# 3_amplifier.net
KiCad netlist of a schematic drawn in Altium Designer
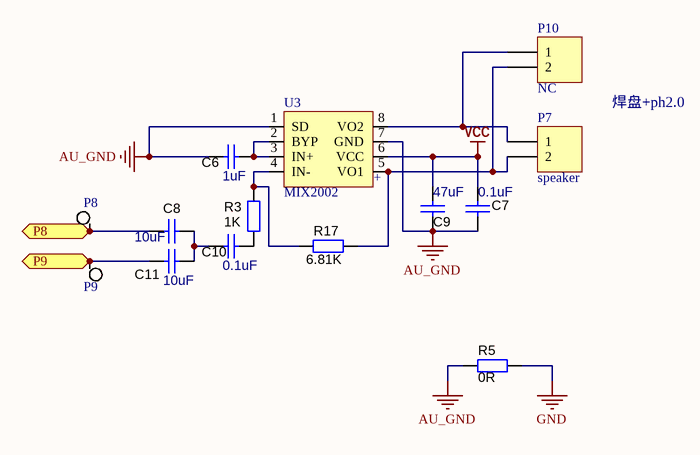
[diagram p0: 3 amplifier.SchDoc]

(export (version "E")
  (design (tool "Eeschema 10.0.6"))
  (components
    (comp (ref "C6")
      (value "1uF")
      (footprint "0402")
      (description "CAP, CERM, 0.01uF, 100V, +/-5%, X7R, 0603")
      (fields (field (name "PARTNUMBER") "06031C103JAT2A") (field (name "MANUFACTURER") "AVX"))
      (libsource (lib "03.常用器件") (part "CAP1_npol"))
    )
    (comp (ref "C7")
      (value "0.1uF")
      (footprint "0402")
      (description "CAP, CERM, 0.01uF, 100V, +/-5%, X7R, 0603")
      (fields (field (name "PARTNUMBER") "06031C103JAT2A") (field (name "MANUFACTURER") "AVX"))
      (libsource (lib "03.常用器件") (part "CAP1_npol"))
    )
    (comp (ref "C8")
      (value "10uF")
      (footprint "0603")
      (description "CAP, CERM, 0.01uF, 100V, +/-5%, X7R, 0603")
      (fields (field (name "PARTNUMBER") "06031C103JAT2A") (field (name "MANUFACTURER") "AVX"))
      (libsource (lib "03.常用器件") (part "CAP1_npol"))
    )
    (comp (ref "C9")
      (value "47uF")
      (footprint "0805")
      (description "CAP, CERM, 0.01uF, 100V, +/-5%, X7R, 0603")
      (fields (field (name "PARTNUMBER") "06031C103JAT2A") (field (name "MANUFACTURER") "AVX"))
      (libsource (lib "03.常用器件") (part "CAP1_npol"))
    )
    (comp (ref "C10")
      (value "0.1uF")
      (footprint "0402")
      (description "CAP, CERM, 0.01uF, 100V, +/-5%, X7R, 0603")
      (fields (field (name "PARTNUMBER") "06031C103JAT2A") (field (name "MANUFACTURER") "AVX"))
      (libsource (lib "03.常用器件") (part "CAP1_npol"))
    )
    (comp (ref "C11")
      (value "10uF")
      (footprint "0603")
      (description "CAP, CERM, 0.01uF, 100V, +/-5%, X7R, 0603")
      (fields (field (name "PARTNUMBER") "06031C103JAT2A") (field (name "MANUFACTURER") "AVX"))
      (libsource (lib "03.常用器件") (part "CAP1_npol"))
    )
    (comp (ref "P7")
      (value "speaker")
      (footprint "焊盘")
      (description "Header, 2-Pin")
      (fields (field (name "PUBLISHER") "Altium Limited"))
      (libsource (lib "Miscellaneous Connectors") (part "Header 2"))
    )
    (comp (ref "P8")
      (value "~")
      (footprint "测试点")
      (description "Test Point")
      (libsource (lib "my_Schlib") (part "TP"))
    )
    (comp (ref "P9")
      (value "~")
      (footprint "测试点")
      (description "Test Point")
      (libsource (lib "my_Schlib") (part "TP"))
    )
    (comp (ref "P10")
      (value "NC")
      (footprint "2PIN/2.0MM座子")
      (description "Header, 2-Pin")
      (fields (field (name "PUBLISHER") "Altium Limited"))
      (libsource (lib "Miscellaneous Connectors") (part "Header 2"))
    )
    (comp (ref "R3")
      (value "1K")
      (footprint "0402")
      (description "RES, 1.0k ohm, 5%, 0.1W, 0603")
      (fields
        (field (name "PARTNUMBER") "RC0603JR-071KL")
        (field (name "MANUFACTURER") "Yageo America")
        (field (name "PUBLISHER") "Texas Instruments")
      )
      (libsource (lib "") (part "RES1_1"))
    )
    (comp (ref "R5")
      (value "0R")
      (footprint "0402")
      (description "RES, 1.0k ohm, 5%, 0.1W, 0603")
      (fields
        (field (name "PARTNUMBER") "RC0603JR-071KL")
        (field (name "MANUFACTURER") "Yageo America")
        (field (name "PUBLISHER") "Texas Instruments")
      )
      (libsource (lib "03.常用器件") (part "RES1"))
    )
    (comp (ref "R17")
      (value "6.81K")
      (footprint "0402")
      (description "RES, 1.0k ohm, 5%, 0.1W, 0603")
      (fields
        (field (name "PARTNUMBER") "RC0603JR-071KL")
        (field (name "MANUFACTURER") "Yageo America")
        (field (name "PUBLISHER") "Texas Instruments")
      )
      (libsource (lib "") (part "RES1_2"))
    )
    (comp (ref "U3") (value "MIX2002") (footprint "SOP-8") (libsource (lib "Schlib1") (part "MIX2002")))
  )
  (nets
    (net (code "1") (name "/P8") (class "Default")
      (node (ref "C8") (pin "2") (pinfunction "2_2") (pintype "passive"))
      (node (ref "P8") (pin "1") (pinfunction "1_1") (pintype "passive"))
    )
    (net (code "2") (name "/P9") (class "Default")
      (node (ref "C11") (pin "2") (pinfunction "2_2") (pintype "passive"))
      (node (ref "P9") (pin "1") (pinfunction "1_1") (pintype "passive"))
    )
    (net (code "3") (name "AU_GND") (class "Default")
      (node (ref "C6") (pin "1") (pinfunction "1_1") (pintype "passive"))
      (node (ref "C7") (pin "2") (pinfunction "2_2") (pintype "passive"))
      (node (ref "C9") (pin "2") (pinfunction "2_2") (pintype "passive"))
      (node (ref "R5") (pin "2") (pinfunction "2_2") (pintype "passive"))
      (node (ref "U3") (pin "1") (pinfunction "SD_1") (pintype "passive"))
      (node (ref "U3") (pin "7") (pinfunction "GND_7") (pintype "passive"))
    )
    (net (code "4") (name "GND") (class "Default")
      (node (ref "R5") (pin "1") (pinfunction "1_1") (pintype "passive"))
    )
    (net (code "5") (name "Net-(C10-Pad1)") (class "Default")
      (node (ref "C10") (pin "1") (pinfunction "1_1") (pintype "passive"))
      (node (ref "C11") (pin "1") (pinfunction "1_1") (pintype "passive"))
      (node (ref "C8") (pin "1") (pinfunction "1_1") (pintype "passive"))
    )
    (net (code "6") (name "Net-(C10-Pad2)") (class "Default")
      (node (ref "C10") (pin "2") (pinfunction "2_2") (pintype "passive"))
      (node (ref "R3") (pin "1") (pinfunction "1_1") (pintype "passive"))
    )
    (net (code "7") (name "Net-(U3-BYP)") (class "Default")
      (node (ref "C6") (pin "2") (pinfunction "2_2") (pintype "passive"))
      (node (ref "U3") (pin "2") (pinfunction "BYP_2") (pintype "passive"))
      (node (ref "U3") (pin "3") (pinfunction "IN+_3") (pintype "passive"))
    )
    (net (code "8") (name "Net-(U3-IN-)") (class "Default")
      (node (ref "R17") (pin "1") (pinfunction "1_1") (pintype "passive"))
      (node (ref "R3") (pin "2") (pinfunction "2_2") (pintype "passive"))
      (node (ref "U3") (pin "4") (pinfunction "IN-_4") (pintype "passive"))
    )
    (net (code "9") (name "Net-(U3-VO1)") (class "Default")
      (node (ref "P10") (pin "2") (pinfunction "2_2") (pintype "passive"))
      (node (ref "P7") (pin "2") (pinfunction "2_2") (pintype "passive"))
      (node (ref "R17") (pin "2") (pinfunction "2_2") (pintype "passive"))
      (node (ref "U3") (pin "5") (pinfunction "VO1_5") (pintype "passive"))
    )
    (net (code "10") (name "Net-(U3-VO2)") (class "Default")
      (node (ref "P10") (pin "1") (pinfunction "1_1") (pintype "passive"))
      (node (ref "P7") (pin "1") (pinfunction "1_1") (pintype "passive"))
      (node (ref "U3") (pin "8") (pinfunction "VO2_8") (pintype "passive"))
    )
    (net (code "11") (name "VCC") (class "Default")
      (node (ref "C7") (pin "1") (pinfunction "1_1") (pintype "passive"))
      (node (ref "C9") (pin "1") (pinfunction "1_1") (pintype "passive"))
      (node (ref "U3") (pin "6") (pinfunction "VCC_6") (pintype "passive"))
    )
  )
)
